# iF11P.net
KiCad netlist of a schematic drawn in Altium Designer
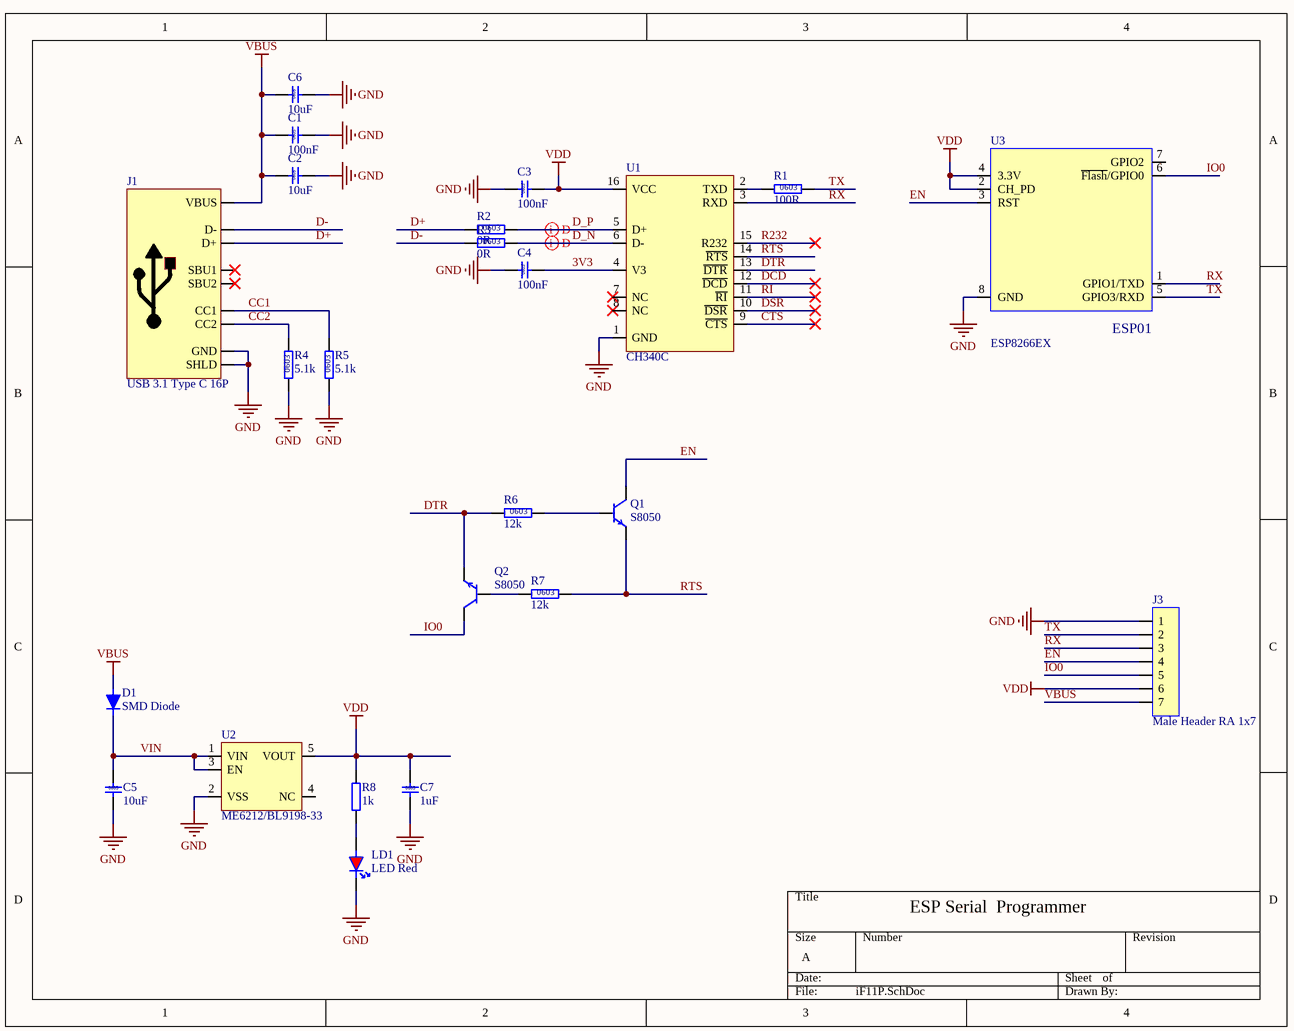
[diagram p0: iF11P.SchDoc]

(export (version "E")
  (design (tool "Eeschema 10.0.6"))
  (components
    (comp (ref "C1")
      (value "100nF")
      (footprint "C0603")
      (description "10% 16V")
      (fields (field (name "PART NO") "W-T-CA-X703N100K50VNT") (field (name "MANUFACTURER") "FENGHUA"))
      (libsource (lib "Rescap") (part "C 0603 100nF 50V"))
    )
    (comp (ref "C2")
      (value "10uF")
      (footprint "C0805")
      (description "10% 25V")
      (fields (field (name "PART NO") "WP0005368"))
      (libsource (lib "Rescap") (part "C 0805 10uF 25V"))
    )
    (comp (ref "C3")
      (value "100nF")
      (footprint "C0603")
      (description "10% 16V")
      (fields (field (name "PART NO") "W-T-CA-X703N100K50VNT") (field (name "MANUFACTURER") "FENGHUA"))
      (libsource (lib "Rescap") (part "C 0603 100nF 50V"))
    )
    (comp (ref "C4")
      (value "100nF")
      (footprint "C0603")
      (description "10% 16V")
      (fields (field (name "PART NO") "W-T-CA-X703N100K50VNT") (field (name "MANUFACTURER") "FENGHUA"))
      (libsource (lib "Rescap") (part "C 0603 100nF 50V"))
    )
    (comp (ref "C5")
      (value "10uF")
      (footprint "C0805")
      (description "10% 25V")
      (fields (field (name "PART NO") "WP0005368"))
      (libsource (lib "Rescap") (part "C 0805 10uF 25V"))
    )
    (comp (ref "C6")
      (value "10uF")
      (footprint "C0805")
      (description "10% 25V")
      (fields (field (name "PART NO") "WP0005368"))
      (libsource (lib "Rescap") (part "C 0805 10uF 25V"))
    )
    (comp (ref "C7")
      (value "1uF")
      (footprint "C0603")
      (description "10% 25V")
      (fields (field (name "PART NO") "W-T-CA-X703U001K25VNT"))
      (libsource (lib "Rescap") (part "C 0603 1uF 25V"))
    )
    (comp (ref "D1")
      (value "SMD Diode")
      (footprint "SOD-323")
      (libsource (lib "Rectifier") (part "Diode-smd"))
    )
    (comp (ref "J1")
      (value "USB 3.1 Type C 16P")
      (footprint "USBC-16P")
      (description "TYPE-C 16PIN L8.35")
      (fields (field (name "PART NO") "W-T-CN-TYPE-C 16P"))
      (libsource (lib "Connector") (part "USB-C-16P"))
    )
    (comp (ref "J3")
      (value "Male Header RA 1x7")
      (footprint "MHEADER-RA-1x7")
      (description "7 Pin Male Header Bent/RA")
      (libsource (lib "Connector") (part "MHeader-RA-1x7"))
    )
    (comp (ref "LD1")
      (value "LED Red")
      (footprint "LED-0603-RED")
      (libsource (lib "Optoelectronics") (part "LED Red"))
    )
    (comp (ref "Q1") (value "S8050") (footprint "SOT23") (libsource (lib "Transistor") (part "NPN-SOT-23")))
    (comp (ref "Q2") (value "S8050") (footprint "SOT23") (libsource (lib "Transistor") (part "NPN-SOT-23")))
    (comp (ref "R1")
      (value "100R")
      (footprint "R0603-LD")
      (description "5%")
      (fields (field (name "PART NO") "W-T-RE-RS03K101JT"))
      (libsource (lib "Rescap") (part "R 0603 100R"))
    )
    (comp (ref "R2")
      (value "0R")
      (footprint "R0603-LD")
      (description "5%")
      (fields (field (name "PART NO") "W-T-RE-RS03K0RJT") (field (name "MANUFACTURER") "贴片"))
      (libsource (lib "Rescap") (part "R 0603 0R"))
    )
    (comp (ref "R3")
      (value "0R")
      (footprint "R0603-LD")
      (description "5%")
      (fields (field (name "PART NO") "W-T-RE-RS03K0RJT") (field (name "MANUFACTURER") "贴片"))
      (libsource (lib "Rescap") (part "R 0603 0R"))
    )
    (comp (ref "R4")
      (value "5.1k")
      (footprint "R0603-LD")
      (description "5%")
      (fields (field (name "PART NO") "W-T-RE-RS03K512JT"))
      (libsource (lib "Rescap") (part "R 0603 5.1k"))
    )
    (comp (ref "R5")
      (value "5.1k")
      (footprint "R0603-LD")
      (description "5%")
      (fields (field (name "PART NO") "W-T-RE-RS03K512JT"))
      (libsource (lib "Rescap") (part "R 0603 5.1k"))
    )
    (comp (ref "R6")
      (value "12k")
      (footprint "R0603-LD")
      (description "5%")
      (fields (field (name "PART NO") "W-T-RE-RS03K123JT"))
      (libsource (lib "Rescap") (part "R 0603 12k"))
    )
    (comp (ref "R7")
      (value "12k")
      (footprint "R0603-LD")
      (description "5%")
      (fields (field (name "PART NO") "W-T-RE-RS03K123JT"))
      (libsource (lib "Rescap") (part "R 0603 12k"))
    )
    (comp (ref "R8")
      (value "1k")
      (footprint "R0805")
      (description "1206")
      (libsource (lib "Resistor") (part "Resistor"))
    )
    (comp (ref "U1")
      (value "CH340C")
      (footprint "SOP16-5.6-1.27")
      (description "USB to Serial Port chip")
      (libsource (lib "mylib2") (part "CH340C"))
    )
    (comp (ref "U2")
      (value "ME6212/BL9198-33")
      (footprint "SOT23-5")
      (libsource (lib "Others") (part "ME6211C28M5G"))
    )
    (comp (ref "U3") (value "ESP8266EX") (footprint "ESP-01") (libsource (lib "module") (part "ESP01")))
  )
  (nets
    (net (code "1") (name "/3V3") (class "Default")
      (node (ref "C4") (pin "2") (pinfunction "2_2") (pintype "passive"))
      (node (ref "U1") (pin "4") (pinfunction "V3_4") (pintype "passive"))
    )
    (net (code "2") (name "/CC1") (class "Default")
      (node (ref "J1") (pin "4") (pinfunction "CC1_4") (pintype "passive"))
      (node (ref "R5") (pin "2") (pinfunction "2_2") (pintype "passive"))
    )
    (net (code "3") (name "/CC2") (class "Default")
      (node (ref "J1") (pin "8") (pinfunction "CC2_8") (pintype "passive"))
      (node (ref "R4") (pin "2") (pinfunction "2_2") (pintype "passive"))
    )
    (net (code "4") (name "/CTS") (class "Default")
      (node (ref "U1") (pin "9") (pinfunction "~{CTS}_9") (pintype "passive+no_connect"))
    )
    (net (code "5") (name "/D+") (class "Default")
      (node (ref "J1") (pin "6") (pinfunction "D+_6") (pintype "passive"))
      (node (ref "R2") (pin "1") (pinfunction "1_1") (pintype "passive"))
    )
    (net (code "6") (name "/D-") (class "Default")
      (node (ref "J1") (pin "5") (pinfunction "D-_5") (pintype "passive"))
      (node (ref "R3") (pin "1") (pinfunction "1_1") (pintype "passive"))
    )
    (net (code "7") (name "/DCD") (class "Default")
      (node (ref "U1") (pin "12") (pinfunction "~{DCD}_12") (pintype "passive+no_connect"))
    )
    (net (code "8") (name "/DSR") (class "Default")
      (node (ref "U1") (pin "10") (pinfunction "~{DSR}_10") (pintype "passive+no_connect"))
    )
    (net (code "9") (name "/DTR") (class "Default")
      (node (ref "Q2") (pin "2") (pinfunction "E_2") (pintype "passive"))
      (node (ref "R6") (pin "1") (pinfunction "1_1") (pintype "passive"))
      (node (ref "U1") (pin "13") (pinfunction "~{DTR}_13") (pintype "passive"))
    )
    (net (code "10") (name "/D_N") (class "Default")
      (node (ref "R3") (pin "2") (pinfunction "2_2") (pintype "passive"))
      (node (ref "U1") (pin "6") (pinfunction "D-_6") (pintype "passive"))
    )
    (net (code "11") (name "/D_P") (class "Default")
      (node (ref "R2") (pin "2") (pinfunction "2_2") (pintype "passive"))
      (node (ref "U1") (pin "5") (pinfunction "D+_5") (pintype "passive"))
    )
    (net (code "12") (name "/EN") (class "Default")
      (node (ref "J3") (pin "4") (pinfunction "4_4") (pintype "passive"))
      (node (ref "Q1") (pin "3") (pinfunction "C_3") (pintype "passive"))
      (node (ref "U3") (pin "3") (pinfunction "RST_3") (pintype "passive"))
    )
    (net (code "13") (name "/IO0") (class "Default")
      (node (ref "J3") (pin "5") (pinfunction "5_5") (pintype "passive"))
      (node (ref "Q2") (pin "3") (pinfunction "C_3") (pintype "passive"))
      (node (ref "U3") (pin "6") (pinfunction "~{Flash}/GPIO0_6") (pintype "passive"))
    )
    (net (code "14") (name "/R232") (class "Default")
      (node (ref "U1") (pin "15") (pinfunction "R232_15") (pintype "passive+no_connect"))
    )
    (net (code "15") (name "/RI") (class "Default")
      (node (ref "U1") (pin "11") (pinfunction "~{RI}_11") (pintype "passive+no_connect"))
    )
    (net (code "16") (name "/RTS") (class "Default")
      (node (ref "Q1") (pin "2") (pinfunction "E_2") (pintype "passive"))
      (node (ref "R7") (pin "2") (pinfunction "2_2") (pintype "passive"))
      (node (ref "U1") (pin "14") (pinfunction "~{RTS}_14") (pintype "passive"))
    )
    (net (code "17") (name "/RX") (class "Default")
      (node (ref "J3") (pin "3") (pinfunction "3_3") (pintype "passive"))
      (node (ref "U1") (pin "3") (pinfunction "RXD_3") (pintype "passive"))
      (node (ref "U3") (pin "1") (pinfunction "GPIO1/TXD_1") (pintype "passive"))
    )
    (net (code "18") (name "/TX") (class "Default")
      (node (ref "J3") (pin "2") (pinfunction "2_2") (pintype "passive"))
      (node (ref "R1") (pin "2") (pinfunction "2_2") (pintype "passive"))
      (node (ref "U3") (pin "5") (pinfunction "GPIO3/RXD_5") (pintype "passive"))
    )
    (net (code "19") (name "/VIN") (class "Default")
      (node (ref "C5") (pin "1") (pinfunction "1_1") (pintype "passive"))
      (node (ref "D1") (pin "2") (pinfunction "K_2") (pintype "passive"))
      (node (ref "U2") (pin "1") (pinfunction "VIN_1") (pintype "passive"))
      (node (ref "U2") (pin "3") (pinfunction "EN_3") (pintype "passive"))
    )
    (net (code "20") (name "GND") (class "Default")
      (node (ref "C1") (pin "2") (pinfunction "2_2") (pintype "passive"))
      (node (ref "C2") (pin "2") (pinfunction "2_2") (pintype "passive"))
      (node (ref "C3") (pin "1") (pinfunction "1_1") (pintype "passive"))
      (node (ref "C4") (pin "1") (pinfunction "1_1") (pintype "passive"))
      (node (ref "C5") (pin "2") (pinfunction "2_2") (pintype "passive"))
      (node (ref "C6") (pin "2") (pinfunction "2_2") (pintype "passive"))
      (node (ref "C7") (pin "2") (pinfunction "2_2") (pintype "passive"))
      (node (ref "J1") (pin "1") (pinfunction "GND_1") (pintype "passive"))
      (node (ref "J1") (pin "10") (pinfunction "SHLD_10") (pintype "passive"))
      (node (ref "J3") (pin "1") (pinfunction "1_1") (pintype "passive"))
      (node (ref "LD1") (pin "2") (pinfunction "K_2") (pintype "passive"))
      (node (ref "R4") (pin "1") (pinfunction "1_1") (pintype "passive"))
      (node (ref "R5") (pin "1") (pinfunction "1_1") (pintype "passive"))
      (node (ref "U1") (pin "1") (pinfunction "GND_1") (pintype "passive"))
      (node (ref "U2") (pin "2") (pinfunction "VSS_2") (pintype "passive"))
      (node (ref "U3") (pin "8") (pinfunction "GND_8") (pintype "passive"))
    )
    (net (code "21") (name "Net-(LD1-A)") (class "Default")
      (node (ref "LD1") (pin "1") (pinfunction "A_1") (pintype "passive"))
      (node (ref "R8") (pin "1") (pinfunction "1_1") (pintype "passive"))
    )
    (net (code "22") (name "Net-(Q1-B)") (class "Default")
      (node (ref "Q1") (pin "1") (pinfunction "B_1") (pintype "passive"))
      (node (ref "R6") (pin "2") (pinfunction "2_2") (pintype "passive"))
    )
    (net (code "23") (name "Net-(Q2-B)") (class "Default")
      (node (ref "Q2") (pin "1") (pinfunction "B_1") (pintype "passive"))
      (node (ref "R7") (pin "1") (pinfunction "1_1") (pintype "passive"))
    )
    (net (code "24") (name "Net-(U1-TXD)") (class "Default")
      (node (ref "R1") (pin "1") (pinfunction "1_1") (pintype "passive"))
      (node (ref "U1") (pin "2") (pinfunction "TXD_2") (pintype "passive"))
    )
    (net (code "25") (name "VBUS") (class "Default")
      (node (ref "C1") (pin "1") (pinfunction "1_1") (pintype "passive"))
      (node (ref "C2") (pin "1") (pinfunction "1_1") (pintype "passive"))
      (node (ref "C6") (pin "1") (pinfunction "1_1") (pintype "passive"))
      (node (ref "D1") (pin "1") (pinfunction "A_1") (pintype "passive"))
      (node (ref "J1") (pin "2") (pinfunction "VBUS_2") (pintype "passive"))
      (node (ref "J3") (pin "7") (pinfunction "7_7") (pintype "passive"))
    )
    (net (code "26") (name "VDD") (class "Default")
      (node (ref "C3") (pin "2") (pinfunction "2_2") (pintype "passive"))
      (node (ref "C7") (pin "1") (pinfunction "1_1") (pintype "passive"))
      (node (ref "J3") (pin "6") (pinfunction "6_6") (pintype "passive"))
      (node (ref "R8") (pin "2") (pinfunction "2_2") (pintype "passive"))
      (node (ref "U1") (pin "16") (pinfunction "VCC_16") (pintype "passive"))
      (node (ref "U2") (pin "5") (pinfunction "VOUT_5") (pintype "passive"))
      (node (ref "U3") (pin "2") (pinfunction "CH_PD_2") (pintype "passive"))
      (node (ref "U3") (pin "4") (pinfunction "3.3V_4") (pintype "passive"))
    )
    (net (code "27") (name "unconnected-(J1-SBU1-Pad7)") (class "Default")
      (node (ref "J1") (pin "7") (pinfunction "SBU1_7") (pintype "passive+no_connect"))
    )
    (net (code "28") (name "unconnected-(J1-SBU2-Pad3)") (class "Default")
      (node (ref "J1") (pin "3") (pinfunction "SBU2_3") (pintype "passive+no_connect"))
    )
    (net (code "29") (name "unconnected-(U1-NC-Pad7)") (class "Default")
      (node (ref "U1") (pin "7") (pinfunction "NC_7") (pintype "passive+no_connect"))
    )
    (net (code "30") (name "unconnected-(U1-NC-Pad8)") (class "Default")
      (node (ref "U1") (pin "8") (pinfunction "NC_8") (pintype "passive+no_connect"))
    )
    (net (code "31") (name "unconnected-(U2-NC-Pad4)") (class "Default")
      (node (ref "U2") (pin "4") (pinfunction "NC_4") (pintype "passive"))
    )
    (net (code "32") (name "unconnected-(U3-GPIO2-Pad7)") (class "Default")
      (node (ref "U3") (pin "7") (pinfunction "GPIO2_7") (pintype "passive"))
    )
  )
)
